# SparkFun_Qwiic_Micro_Accelerometer_BMA40.net
KiCad netlist of a schematic drawn in EAGLE
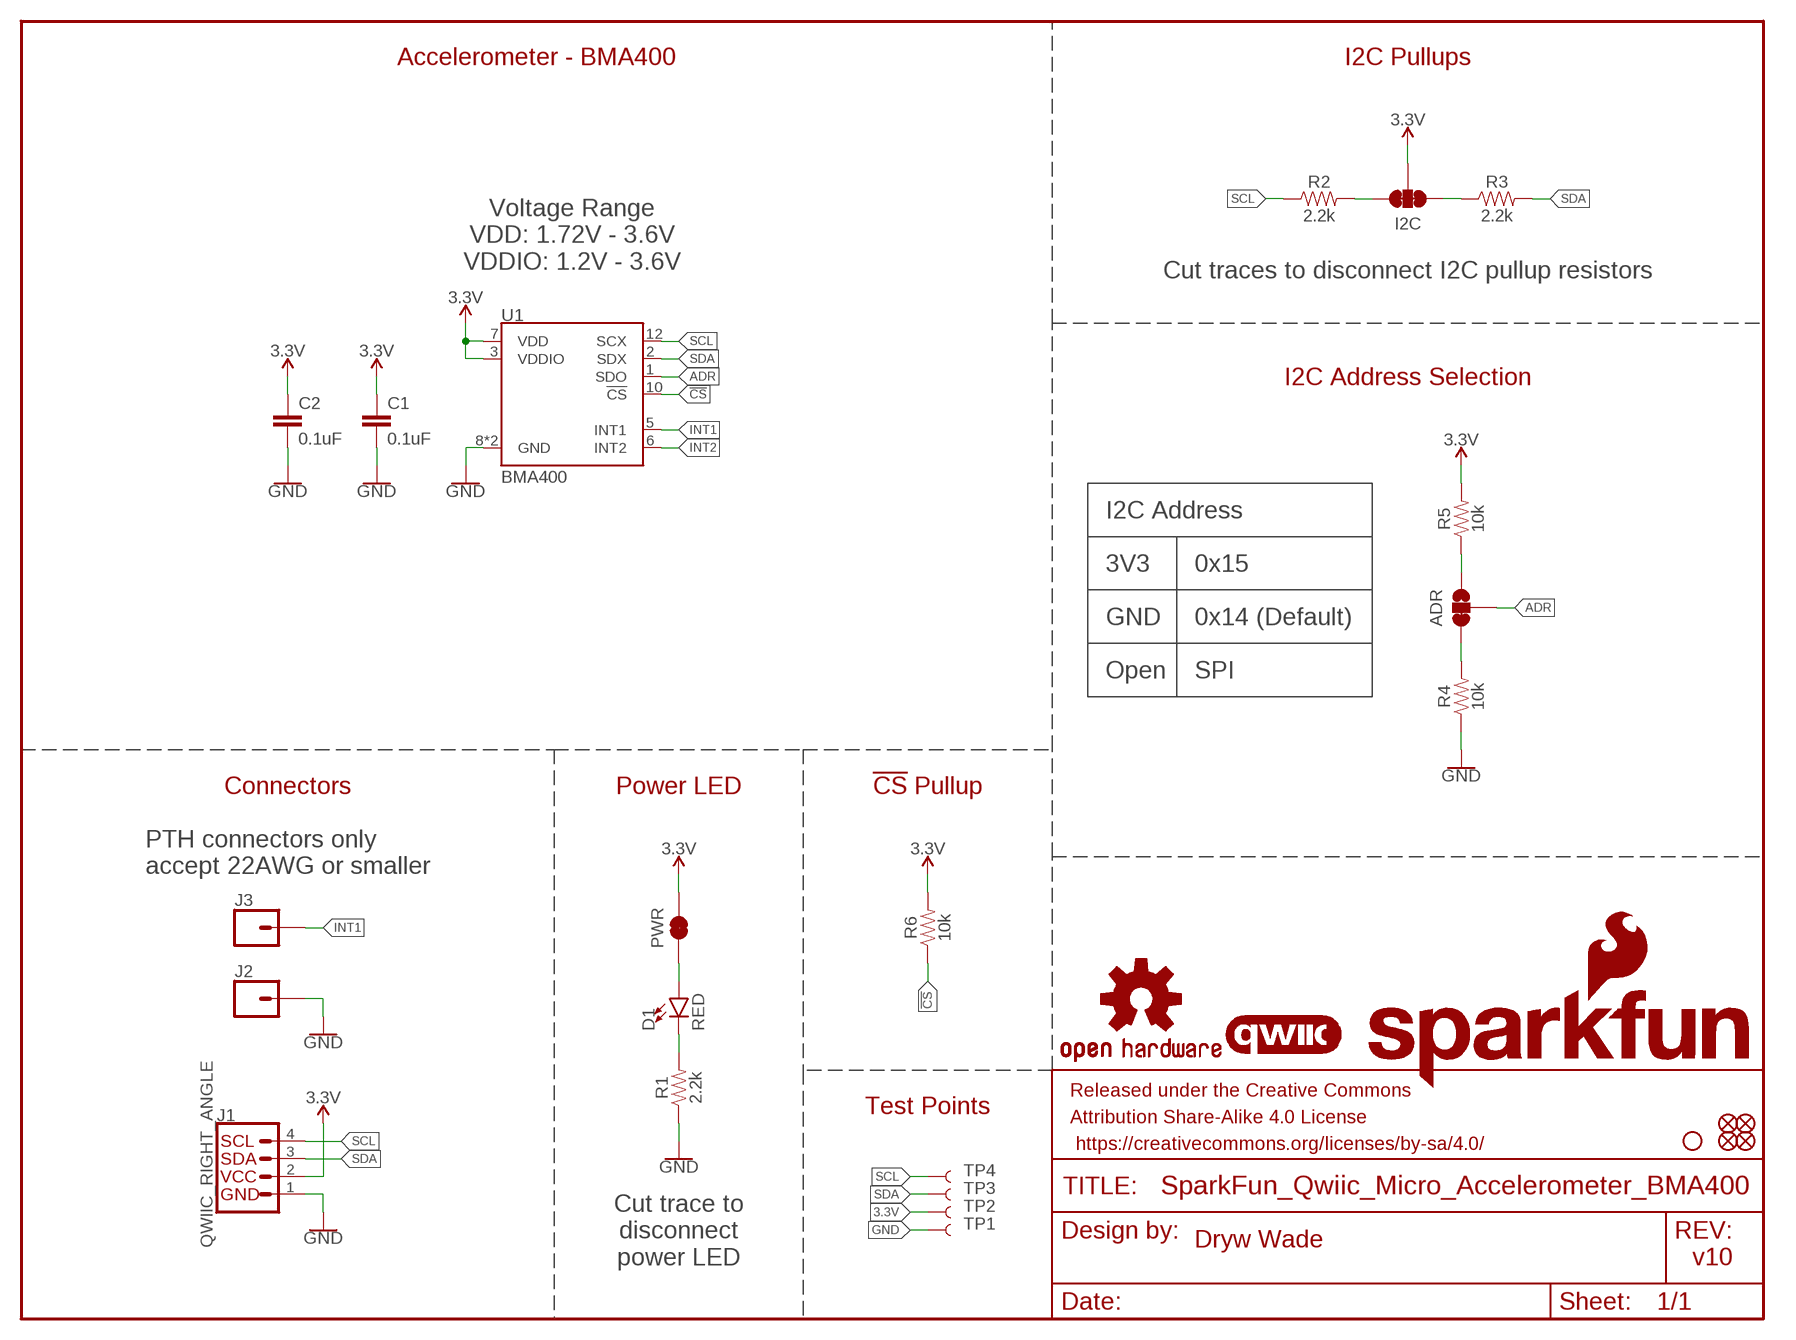
[diagram p0: schematic, sheet 1]

(export (version "E")
  (design (tool "Eeschema 10.0.6"))
  (components
    (comp (ref "ADR")
      (value "JUMPER-SMT_3_1-NC_TRACE_SILK")
      (footprint "eagle-import:SMT-JUMPER_3_1-NC_TRACE_SILK")
      (libsource (lib "eagle-import") (part "JUMPER-SMT_3_1-NC_TRACE_SILK"))
    )
    (comp (ref "C1")
      (value "0.1uF")
      (footprint "eagle-import:0402-TIGHT")
      (libsource (lib "eagle-import") (part "0.1UF-0402T-16V-10%"))
    )
    (comp (ref "C2")
      (value "0.1uF")
      (footprint "eagle-import:0402-TIGHT")
      (libsource (lib "eagle-import") (part "0.1UF-0402T-16V-10%"))
    )
    (comp (ref "D1")
      (value "RED")
      (footprint "eagle-import:LED-0402")
      (libsource (lib "eagle-import") (part "LED-RED_0402"))
    )
    (comp (ref "FD1")
      (value "FIDUCIALUFIDUCIAL")
      (footprint "eagle-import:FIDUCIAL-MICRO")
      (libsource (lib "eagle-import") (part "FIDUCIALUFIDUCIAL"))
    )
    (comp (ref "FD2")
      (value "FIDUCIALUFIDUCIAL")
      (footprint "eagle-import:FIDUCIAL-MICRO")
      (libsource (lib "eagle-import") (part "FIDUCIALUFIDUCIAL"))
    )
    (comp (ref "FD3")
      (value "FIDUCIALUFIDUCIAL")
      (footprint "eagle-import:FIDUCIAL-MICRO")
      (libsource (lib "eagle-import") (part "FIDUCIALUFIDUCIAL"))
    )
    (comp (ref "FD4")
      (value "FIDUCIALUFIDUCIAL")
      (footprint "eagle-import:FIDUCIAL-MICRO")
      (libsource (lib "eagle-import") (part "FIDUCIALUFIDUCIAL"))
    )
    (comp (ref "FRAME1")
      (value "FRAME-LETTER")
      (footprint "eagle-import:CREATIVE_COMMONS")
      (libsource (lib "eagle-import") (part "FRAME-LETTER"))
    )
    (comp (ref "H1")
      (value "STAND-OFF")
      (footprint "eagle-import:STAND-OFF")
      (libsource (lib "eagle-import") (part "STAND-OFF"))
    )
    (comp (ref "I2C")
      (value "JUMPER-SMT_3_2-NC_TRACE_SILK")
      (footprint "eagle-import:SMT-JUMPER_3_2-NC_TRACE_SILK")
      (libsource (lib "eagle-import") (part "JUMPER-SMT_3_2-NC_TRACE_SILK"))
    )
    (comp (ref "J1")
      (value "QWIIC_RIGHT_ANGLE")
      (footprint "eagle-import:JST04_1MM_RA")
      (libsource (lib "eagle-import") (part "QWIIC_CONNECTORJS-1MM"))
    )
    (comp (ref "J2")
      (value "CONN_01_1MM")
      (footprint "eagle-import:1X01_1MM_NO_SILK")
      (libsource (lib "eagle-import") (part "CONN_01_1MM"))
    )
    (comp (ref "J3")
      (value "CONN_01_1MM")
      (footprint "eagle-import:1X01_1MM_NO_SILK")
      (libsource (lib "eagle-import") (part "CONN_01_1MM"))
    )
    (comp (ref "LOGO1")
      (value "QWIIC_LOGO_3MM")
      (footprint "eagle-import:QWIIC_3MM")
      (libsource (lib "eagle-import") (part "QWIIC_LOGO_3MM"))
    )
    (comp (ref "LOGO2")
      (value "SFE_LOGO_NAMEBLANK")
      (footprint "eagle-import:BLANK")
      (libsource (lib "eagle-import") (part "SFE_LOGO_NAMEBLANK"))
    )
    (comp (ref "LOGO3")
      (value "OSHW-LOGOS")
      (footprint "eagle-import:OSHW-LOGO-S")
      (libsource (lib "eagle-import") (part "OSHW-LOGOS"))
    )
    (comp (ref "LOGO4")
      (value "SFE_LOGO_FLAME.1_INCH")
      (footprint "eagle-import:SFE_LOGO_FLAME_.1")
      (libsource (lib "eagle-import") (part "SFE_LOGO_FLAME.1_INCH"))
    )
    (comp (ref "PWR")
      (value "JUMPER-SMT_2_NC_TRACE_SILK")
      (footprint "eagle-import:SMT-JUMPER_2_NC_TRACE_SILK")
      (libsource (lib "eagle-import") (part "JUMPER-SMT_2_NC_TRACE_SILK"))
    )
    (comp (ref "R1")
      (value "2.2k")
      (footprint "eagle-import:0402-TIGHT")
      (libsource (lib "eagle-import") (part "2.2KOHM-0402T-1/16W-1%"))
    )
    (comp (ref "R2")
      (value "2.2k")
      (footprint "eagle-import:0402-TIGHT")
      (libsource (lib "eagle-import") (part "2.2KOHM-0402T-1/16W-1%"))
    )
    (comp (ref "R3")
      (value "2.2k")
      (footprint "eagle-import:0402-TIGHT")
      (libsource (lib "eagle-import") (part "2.2KOHM-0402T-1/16W-1%"))
    )
    (comp (ref "R4")
      (value "10k")
      (footprint "eagle-import:0402-TIGHT")
      (libsource (lib "eagle-import") (part "10KOHM-0402T-1/16W-1%"))
    )
    (comp (ref "R5")
      (value "10k")
      (footprint "eagle-import:0402-TIGHT")
      (libsource (lib "eagle-import") (part "10KOHM-0402T-1/16W-1%"))
    )
    (comp (ref "R6")
      (value "10k")
      (footprint "eagle-import:0402-TIGHT")
      (libsource (lib "eagle-import") (part "10KOHM-0402T-1/16W-1%"))
    )
    (comp (ref "TP1")
      (value "TEST-POINT3")
      (footprint "eagle-import:PAD.03X.03")
      (libsource (lib "eagle-import") (part "TEST-POINT3"))
    )
    (comp (ref "TP2")
      (value "TEST-POINT3")
      (footprint "eagle-import:PAD.03X.03")
      (libsource (lib "eagle-import") (part "TEST-POINT3"))
    )
    (comp (ref "TP3")
      (value "TEST-POINT3")
      (footprint "eagle-import:PAD.03X.03")
      (libsource (lib "eagle-import") (part "TEST-POINT3"))
    )
    (comp (ref "TP4")
      (value "TEST-POINT3")
      (footprint "eagle-import:PAD.03X.03")
      (libsource (lib "eagle-import") (part "TEST-POINT3"))
    )
    (comp (ref "U1")
      (value "BMA400")
      (footprint "eagle-import:BMA400")
      (libsource (lib "eagle-import") (part "BMA400"))
    )
  )
  (nets
    (net (code "1") (name "/~{CS}") (class "Default")
      (node (ref "R6") (pin "1") (pinfunction "1_1") (pintype "passive"))
      (node (ref "U1") (pin "10") (pinfunction "~{CS}_10") (pintype "input"))
    )
    (net (code "2") (name "3.3V") (class "Default")
      (node (ref "C1") (pin "1") (pinfunction "1_1") (pintype "passive"))
      (node (ref "C2") (pin "1") (pinfunction "1_1") (pintype "passive"))
      (node (ref "I2C") (pin "2") (pinfunction "2_2") (pintype "passive"))
      (node (ref "J1") (pin "2") (pinfunction "2_2") (pintype "power_in"))
      (node (ref "PWR") (pin "2") (pinfunction "2_2") (pintype "passive"))
      (node (ref "R5") (pin "2") (pinfunction "2_2") (pintype "passive"))
      (node (ref "R6") (pin "2") (pinfunction "2_2") (pintype "passive"))
      (node (ref "TP2") (pin "1") (pinfunction "1_1") (pintype "bidirectional"))
      (node (ref "U1") (pin "3") (pinfunction "VDDIO_3") (pintype "power_in"))
      (node (ref "U1") (pin "7") (pinfunction "VDD_7") (pintype "power_in"))
    )
    (net (code "3") (name "ADR") (class "Default")
      (node (ref "ADR") (pin "2") (pinfunction "2_2") (pintype "passive"))
      (node (ref "U1") (pin "1") (pinfunction "SDO_1") (pintype "output"))
    )
    (net (code "4") (name "GND") (class "Default")
      (node (ref "C1") (pin "2") (pinfunction "2_2") (pintype "passive"))
      (node (ref "C2") (pin "2") (pinfunction "2_2") (pintype "passive"))
      (node (ref "J1") (pin "1") (pinfunction "1_1") (pintype "power_in"))
      (node (ref "J2") (pin "1") (pinfunction "1_1") (pintype "passive"))
      (node (ref "R1") (pin "1") (pinfunction "1_1") (pintype "passive"))
      (node (ref "R4") (pin "1") (pinfunction "1_1") (pintype "passive"))
      (node (ref "TP1") (pin "1") (pinfunction "1_1") (pintype "bidirectional"))
      (node (ref "U1") (pin "8") (pinfunction "GND_8") (pintype "power_in"))
      (node (ref "U1") (pin "9") (pinfunction "GND_9") (pintype "power_in"))
    )
    (net (code "5") (name "INT1") (class "Default")
      (node (ref "J3") (pin "1") (pinfunction "1_1") (pintype "passive"))
      (node (ref "U1") (pin "5") (pinfunction "INT1_5") (pintype "output"))
    )
    (net (code "6") (name "INT2") (class "Default")
      (node (ref "U1") (pin "6") (pinfunction "INT2_6") (pintype "output"))
    )
    (net (code "7") (name "Net-(ADR-Pad1)") (class "Default")
      (node (ref "ADR") (pin "1") (pinfunction "1_1") (pintype "passive"))
      (node (ref "R5") (pin "1") (pinfunction "1_1") (pintype "passive"))
    )
    (net (code "8") (name "Net-(ADR-Pad3)") (class "Default")
      (node (ref "ADR") (pin "3") (pinfunction "3_3") (pintype "passive"))
      (node (ref "R4") (pin "2") (pinfunction "2_2") (pintype "passive"))
    )
    (net (code "9") (name "Net-(D1-PadA)") (class "Default")
      (node (ref "D1") (pin "A") (pinfunction "A_A") (pintype "passive"))
      (node (ref "PWR") (pin "1") (pinfunction "1_1") (pintype "passive"))
    )
    (net (code "10") (name "Net-(D1-PadC)") (class "Default")
      (node (ref "D1") (pin "C") (pinfunction "C_C") (pintype "passive"))
      (node (ref "R1") (pin "2") (pinfunction "2_2") (pintype "passive"))
    )
    (net (code "11") (name "Net-(I2C-Pad1)") (class "Default")
      (node (ref "I2C") (pin "1") (pinfunction "1_1") (pintype "passive"))
      (node (ref "R3") (pin "1") (pinfunction "1_1") (pintype "passive"))
    )
    (net (code "12") (name "Net-(I2C-Pad3)") (class "Default")
      (node (ref "I2C") (pin "3") (pinfunction "3_3") (pintype "passive"))
      (node (ref "R2") (pin "2") (pinfunction "2_2") (pintype "passive"))
    )
    (net (code "13") (name "SCL") (class "Default")
      (node (ref "J1") (pin "4") (pinfunction "4_4") (pintype "passive"))
      (node (ref "R2") (pin "1") (pinfunction "1_1") (pintype "passive"))
      (node (ref "TP4") (pin "1") (pinfunction "1_1") (pintype "bidirectional"))
      (node (ref "U1") (pin "12") (pinfunction "SCX_12") (pintype "input"))
    )
    (net (code "14") (name "SDA") (class "Default")
      (node (ref "J1") (pin "3") (pinfunction "3_3") (pintype "passive"))
      (node (ref "R3") (pin "2") (pinfunction "2_2") (pintype "passive"))
      (node (ref "TP3") (pin "1") (pinfunction "1_1") (pintype "bidirectional"))
      (node (ref "U1") (pin "2") (pinfunction "SDX_2") (pintype "bidirectional"))
    )
  )
)
